# OBD-II.net
KiCad netlist of a schematic drawn in EAGLE
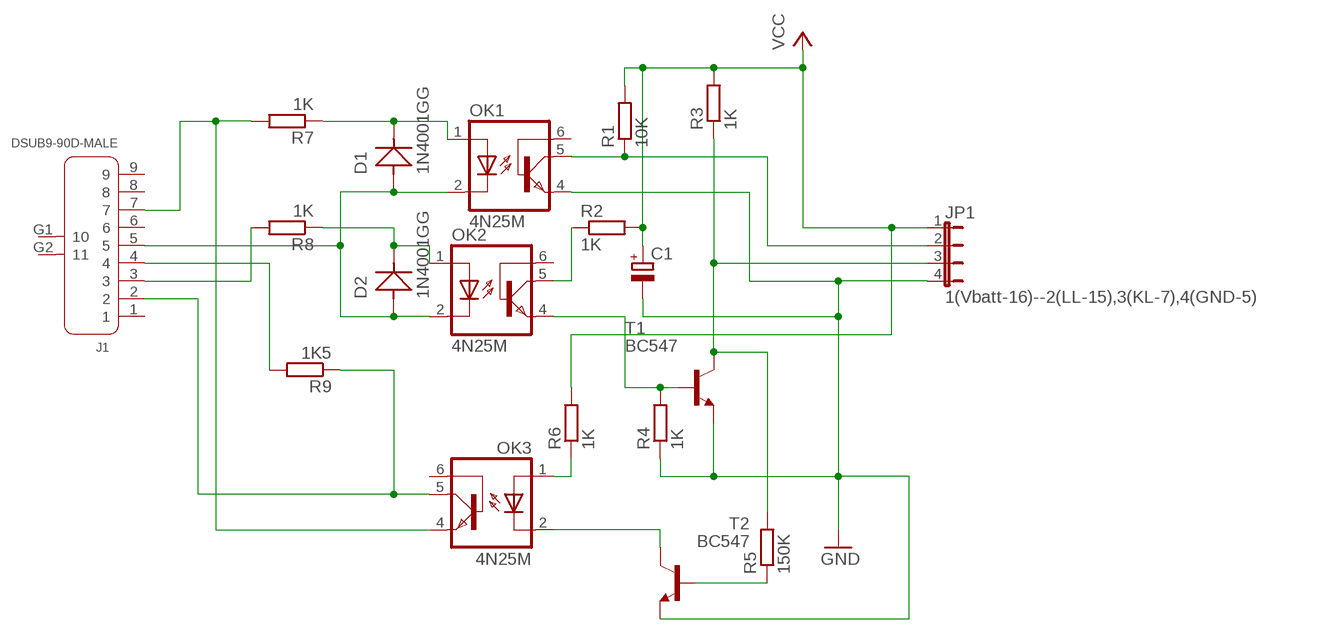
[diagram p0: schematic, sheet 1]

(export (version "E")
  (design (tool "Eeschema 10.0.6"))
  (components
    (comp (ref "C1")
      (value "CPOL-EUE2-5")
      (footprint "eagle-import:E2-5")
      (libsource (lib "eagle-import") (part "CPOL-EUE2-5"))
    )
    (comp (ref "D1")
      (value "1N4001GG")
      (footprint "eagle-import:DO-41")
      (fields (field (name "MANUFACTURER") "ON Semiconductor") (field (name "PART_NUMBER") "1N4001G"))
      (libsource (lib "eagle-import") (part "1N?G4001G"))
    )
    (comp (ref "D2")
      (value "1N4001GG")
      (footprint "eagle-import:DO-41")
      (fields (field (name "MANUFACTURER") "ON Semiconductor") (field (name "PART_NUMBER") "1N4001G"))
      (libsource (lib "eagle-import") (part "1N?G4001G"))
    )
    (comp (ref "J1")
      (value "DSUB9-90D-MALE")
      (footprint "eagle-import:DSUB9+2P-2.77-90D-MALE")
      (libsource (lib "eagle-import") (part "DIP-MALE-DB9-CONNECTOR"))
    )
    (comp (ref "JP1")
      (value "1(Vbatt-16)--2(LL-15),3(KL-7),4(GND-5)")
      (footprint "eagle-import:JP4")
      (libsource (lib "eagle-import") (part "JP4E"))
    )
    (comp (ref "OK1")
      (value "4N25M")
      (footprint "eagle-import:DIL06")
      (fields (field (name "MPN") "4N25-M"))
      (libsource (lib "eagle-import") (part "4N?M25"))
    )
    (comp (ref "OK2")
      (value "4N25M")
      (footprint "eagle-import:DIL06")
      (fields (field (name "MPN") "4N25-M"))
      (libsource (lib "eagle-import") (part "4N?M25"))
    )
    (comp (ref "OK3")
      (value "4N25M")
      (footprint "eagle-import:DIL06")
      (fields (field (name "MPN") "4N25-M"))
      (libsource (lib "eagle-import") (part "4N?M25"))
    )
    (comp (ref "R1")
      (value "10K")
      (footprint "eagle-import:0207_10")
      (libsource (lib "eagle-import") (part "R-EU_0207/10"))
    )
    (comp (ref "R2")
      (value "1K")
      (footprint "eagle-import:0207_10")
      (libsource (lib "eagle-import") (part "R-EU_0207/10"))
    )
    (comp (ref "R3")
      (value "1K")
      (footprint "eagle-import:0207_10")
      (libsource (lib "eagle-import") (part "R-EU_0207/10"))
    )
    (comp (ref "R4")
      (value "1K")
      (footprint "eagle-import:0207_10")
      (libsource (lib "eagle-import") (part "R-EU_0207/10"))
    )
    (comp (ref "R5")
      (value "150K")
      (footprint "eagle-import:0207_10")
      (libsource (lib "eagle-import") (part "R-EU_0207/10"))
    )
    (comp (ref "R6")
      (value "1K")
      (footprint "eagle-import:0207_10")
      (libsource (lib "eagle-import") (part "R-EU_0207/10"))
    )
    (comp (ref "R7")
      (value "1K")
      (footprint "eagle-import:0207_10")
      (libsource (lib "eagle-import") (part "R-EU_0207/10"))
    )
    (comp (ref "R8")
      (value "1K")
      (footprint "eagle-import:0207_10")
      (libsource (lib "eagle-import") (part "R-EU_0207/10"))
    )
    (comp (ref "R9")
      (value "1K5")
      (footprint "eagle-import:0207_10")
      (libsource (lib "eagle-import") (part "R-EU_0207/10"))
    )
    (comp (ref "T1")
      (value "BC547")
      (footprint "eagle-import:TO92")
      (libsource (lib "eagle-import") (part "BC547"))
    )
    (comp (ref "T2")
      (value "BC547")
      (footprint "eagle-import:TO92")
      (libsource (lib "eagle-import") (part "BC547"))
    )
  )
  (nets
    (net (code "1") (name "GND") (class "Default")
      (node (ref "C1") (pin "-") (pinfunction "-_-") (pintype "passive"))
      (node (ref "JP1") (pin "4") (pinfunction "4_4") (pintype "passive"))
      (node (ref "OK1") (pin "4") (pinfunction "EMI_4") (pintype "passive"))
      (node (ref "R4") (pin "1") (pinfunction "1_1") (pintype "passive"))
      (node (ref "T1") (pin "1") (pinfunction "E_1") (pintype "passive"))
      (node (ref "T2") (pin "1") (pinfunction "E_1") (pintype "passive"))
    )
    (net (code "2") (name "Net-(J1-Pad3)") (class "Default")
      (node (ref "J1") (pin "3") (pinfunction "3_3") (pintype "bidirectional"))
      (node (ref "R8") (pin "2") (pinfunction "2_2") (pintype "passive"))
    )
    (net (code "3") (name "Net-(J1-Pad4)") (class "Default")
      (node (ref "J1") (pin "4") (pinfunction "4_4") (pintype "bidirectional"))
      (node (ref "R9") (pin "2") (pinfunction "2_2") (pintype "passive"))
    )
    (net (code "4") (name "Net-(OK1-A)") (class "Default")
      (node (ref "D1") (pin "C") (pinfunction "C_C") (pintype "passive"))
      (node (ref "OK1") (pin "1") (pinfunction "A_1") (pintype "passive"))
      (node (ref "R7") (pin "1") (pinfunction "1_1") (pintype "passive"))
    )
    (net (code "5") (name "Net-(OK1-C)") (class "Default")
      (node (ref "D1") (pin "A") (pinfunction "A_A") (pintype "passive"))
      (node (ref "D2") (pin "A") (pinfunction "A_A") (pintype "passive"))
      (node (ref "J1") (pin "5") (pinfunction "5_5") (pintype "bidirectional"))
      (node (ref "OK1") (pin "2") (pinfunction "C_2") (pintype "passive"))
      (node (ref "OK2") (pin "2") (pinfunction "C_2") (pintype "passive"))
    )
    (net (code "6") (name "Net-(OK1-COL)") (class "Default")
      (node (ref "JP1") (pin "2") (pinfunction "2_2") (pintype "passive"))
      (node (ref "OK1") (pin "5") (pinfunction "COL_5") (pintype "passive"))
      (node (ref "R1") (pin "1") (pinfunction "1_1") (pintype "passive"))
    )
    (net (code "7") (name "Net-(OK2-A)") (class "Default")
      (node (ref "D2") (pin "C") (pinfunction "C_C") (pintype "passive"))
      (node (ref "OK2") (pin "1") (pinfunction "A_1") (pintype "passive"))
      (node (ref "R8") (pin "1") (pinfunction "1_1") (pintype "passive"))
    )
    (net (code "8") (name "Net-(OK2-COL)") (class "Default")
      (node (ref "OK2") (pin "5") (pinfunction "COL_5") (pintype "passive"))
      (node (ref "R2") (pin "1") (pinfunction "1_1") (pintype "passive"))
    )
    (net (code "9") (name "Net-(OK2-EMI)") (class "Default")
      (node (ref "OK2") (pin "4") (pinfunction "EMI_4") (pintype "passive"))
      (node (ref "R4") (pin "2") (pinfunction "2_2") (pintype "passive"))
      (node (ref "T1") (pin "2") (pinfunction "B_2") (pintype "passive"))
    )
    (net (code "10") (name "Net-(OK3-A)") (class "Default")
      (node (ref "OK3") (pin "1") (pinfunction "A_1") (pintype "passive"))
      (node (ref "R6") (pin "1") (pinfunction "1_1") (pintype "passive"))
    )
    (net (code "11") (name "Net-(OK3-C)") (class "Default")
      (node (ref "OK3") (pin "2") (pinfunction "C_2") (pintype "passive"))
      (node (ref "T2") (pin "3") (pinfunction "C_3") (pintype "passive"))
    )
    (net (code "12") (name "Net-(OK3-COL)") (class "Default")
      (node (ref "J1") (pin "2") (pinfunction "2_2") (pintype "bidirectional"))
      (node (ref "OK3") (pin "5") (pinfunction "COL_5") (pintype "passive"))
      (node (ref "R9") (pin "1") (pinfunction "1_1") (pintype "passive"))
    )
    (net (code "13") (name "Net-(OK3-EMI)") (class "Default")
      (node (ref "J1") (pin "7") (pinfunction "7_7") (pintype "bidirectional"))
      (node (ref "OK3") (pin "4") (pinfunction "EMI_4") (pintype "passive"))
      (node (ref "R7") (pin "2") (pinfunction "2_2") (pintype "passive"))
    )
    (net (code "14") (name "Net-(T1-C)") (class "Default")
      (node (ref "JP1") (pin "3") (pinfunction "3_3") (pintype "passive"))
      (node (ref "R3") (pin "1") (pinfunction "1_1") (pintype "passive"))
      (node (ref "R5") (pin "2") (pinfunction "2_2") (pintype "passive"))
      (node (ref "T1") (pin "3") (pinfunction "C_3") (pintype "passive"))
    )
    (net (code "15") (name "Net-(T2-B)") (class "Default")
      (node (ref "R5") (pin "1") (pinfunction "1_1") (pintype "passive"))
      (node (ref "T2") (pin "2") (pinfunction "B_2") (pintype "passive"))
    )
    (net (code "16") (name "VCC") (class "Default")
      (node (ref "C1") (pin "+") (pinfunction "+_+") (pintype "passive"))
      (node (ref "JP1") (pin "1") (pinfunction "1_1") (pintype "passive"))
      (node (ref "R1") (pin "2") (pinfunction "2_2") (pintype "passive"))
      (node (ref "R2") (pin "2") (pinfunction "2_2") (pintype "passive"))
      (node (ref "R3") (pin "2") (pinfunction "2_2") (pintype "passive"))
      (node (ref "R6") (pin "2") (pinfunction "2_2") (pintype "passive"))
    )
    (net (code "17") (name "unconnected-(J1-10-PadG1)") (class "Default")
      (node (ref "J1") (pin "G1") (pinfunction "10_G1") (pintype "bidirectional"))
    )
    (net (code "18") (name "unconnected-(J1-11-PadG2)") (class "Default")
      (node (ref "J1") (pin "G2") (pinfunction "11_G2") (pintype "bidirectional"))
    )
    (net (code "19") (name "unconnected-(J1-Pad1)") (class "Default")
      (node (ref "J1") (pin "1") (pinfunction "1_1") (pintype "bidirectional"))
    )
    (net (code "20") (name "unconnected-(J1-Pad6)") (class "Default")
      (node (ref "J1") (pin "6") (pinfunction "6_6") (pintype "bidirectional"))
    )
    (net (code "21") (name "unconnected-(J1-Pad8)") (class "Default")
      (node (ref "J1") (pin "8") (pinfunction "8_8") (pintype "bidirectional"))
    )
    (net (code "22") (name "unconnected-(J1-Pad9)") (class "Default")
      (node (ref "J1") (pin "9") (pinfunction "9_9") (pintype "bidirectional"))
    )
    (net (code "23") (name "unconnected-(OK1-BAS-Pad6)") (class "Default")
      (node (ref "OK1") (pin "6") (pinfunction "BAS_6") (pintype "passive"))
    )
    (net (code "24") (name "unconnected-(OK2-BAS-Pad6)") (class "Default")
      (node (ref "OK2") (pin "6") (pinfunction "BAS_6") (pintype "passive"))
    )
    (net (code "25") (name "unconnected-(OK3-BAS-Pad6)") (class "Default")
      (node (ref "OK3") (pin "6") (pinfunction "BAS_6") (pintype "passive"))
    )
  )
)
